# Sheet1.net
KiCad netlist of a schematic drawn in Altium Designer
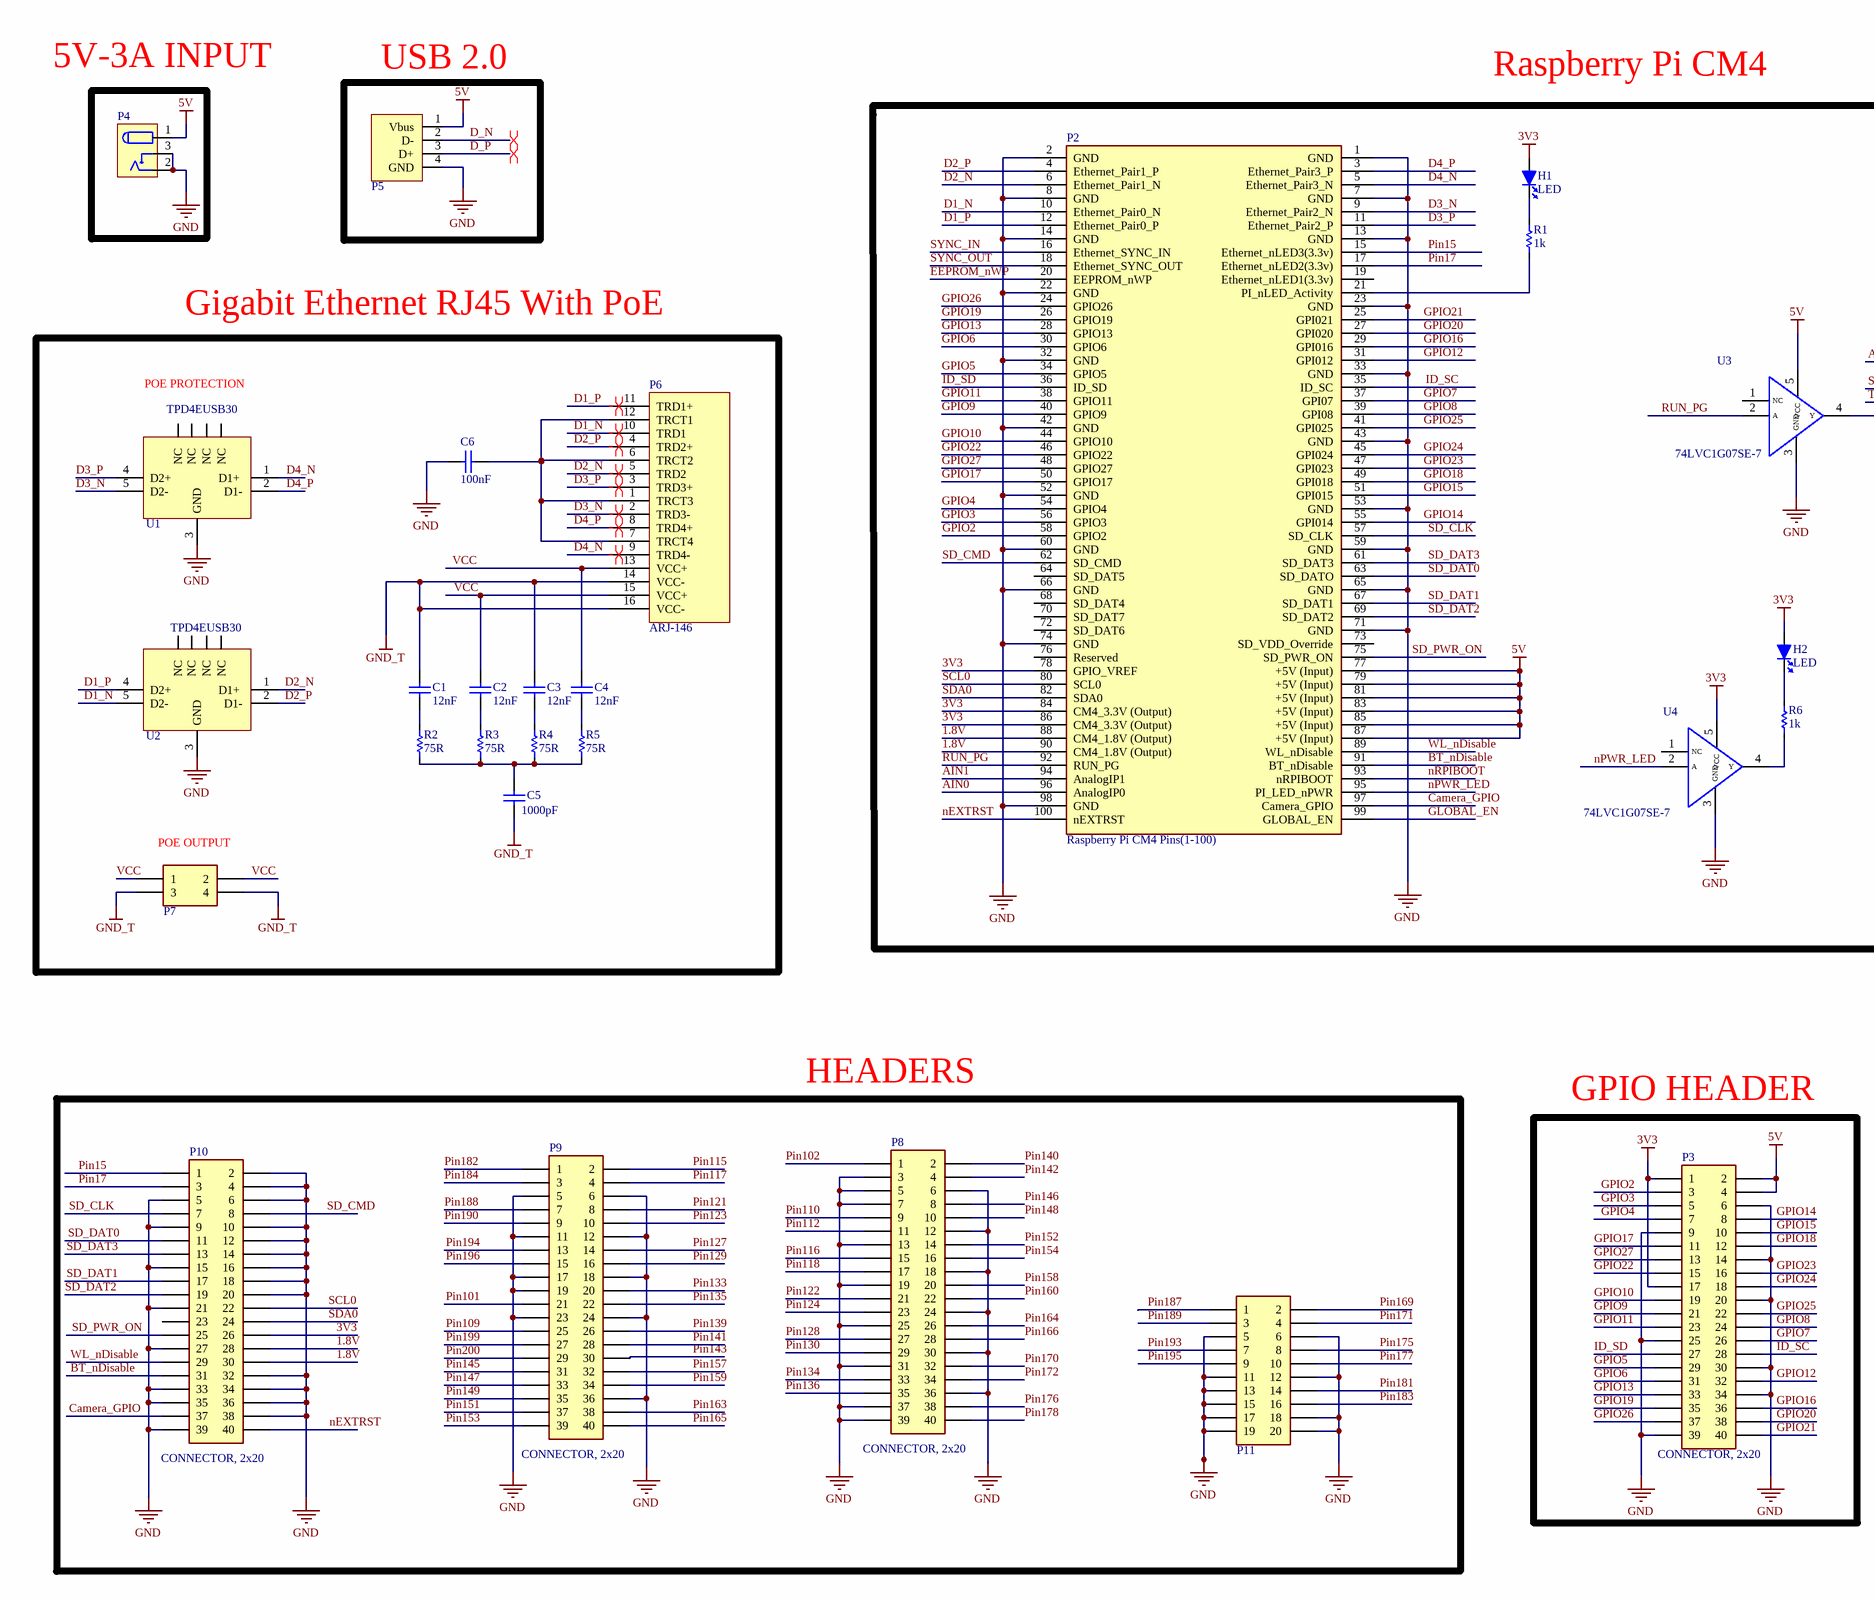
[diagram p0: Sheet1.SchDoc, left]
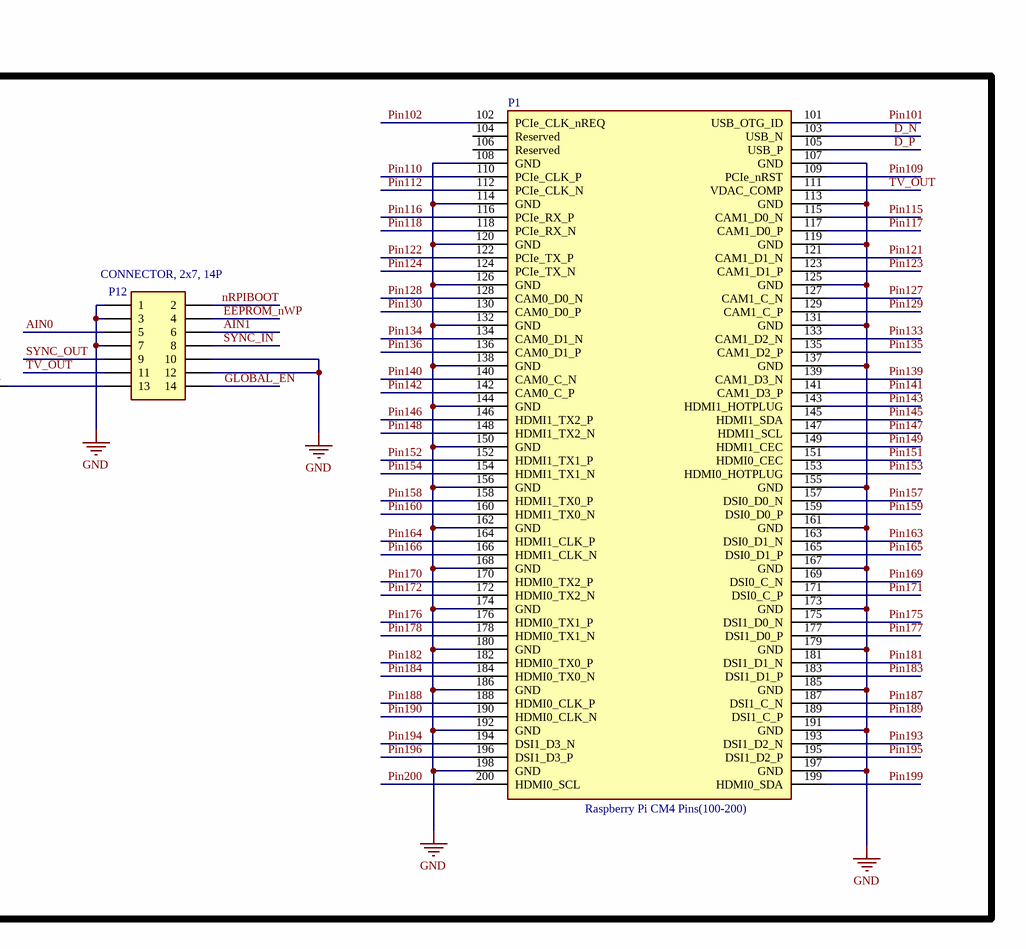
[diagram p1: Sheet1.SchDoc, right]

(export (version "E")
  (design (tool "Eeschema 10.0.6"))
  (components
    (comp (ref "C1")
      (value "12nF")
      (footprint "CC1608-0603L")
      (description "CAP CER 12nF 100V X7R 0603")
      (fields
        (field (name "MANUFACTURER") "KYOCERA AVX")
        (field (name "MANUFACTURER PART NUMBER") "06031C123KAT2A")
      )
      (libsource (lib "SchLibrary") (part "CAPACITOR NON-POL"))
    )
    (comp (ref "C2")
      (value "12nF")
      (footprint "CC1608-0603L")
      (description "CAP CER 12nF 100V X7R 0603")
      (fields
        (field (name "MANUFACTURER") "KYOCERA AVX")
        (field (name "MANUFACTURER PART NUMBER") "06031C123KAT2A")
      )
      (libsource (lib "SchLibrary") (part "CAPACITOR NON-POL"))
    )
    (comp (ref "C3")
      (value "12nF")
      (footprint "CC1608-0603L")
      (description "CAP CER 12nF 100V X7R 0603")
      (fields
        (field (name "MANUFACTURER") "KYOCERA AVX")
        (field (name "MANUFACTURER PART NUMBER") "06031C123KAT2A")
      )
      (libsource (lib "SchLibrary") (part "CAPACITOR NON-POL"))
    )
    (comp (ref "C4")
      (value "12nF")
      (footprint "CC1608-0603L")
      (description "CAP CER 12nF 100V X7R 0603")
      (fields
        (field (name "MANUFACTURER") "KYOCERA AVX")
        (field (name "MANUFACTURER PART NUMBER") "06031C123KAT2A")
      )
      (libsource (lib "SchLibrary") (part "CAPACITOR NON-POL"))
    )
    (comp (ref "C5")
      (value "1000pF")
      (footprint "CC3225-1210L")
      (description "CAP CER 1000pF 2KV X7R 1210")
      (fields
        (field (name "MANUFACTURER") "Johanson Dielectrics Inc.")
        (field (name "MANUFACTURER PART NUMBER") "VPDF202W102K1GV001E")
      )
      (libsource (lib "SchLibrary") (part "CAPACITOR NON-POL"))
    )
    (comp (ref "C6")
      (value "100nF")
      (footprint "CC1608-0603L")
      (description "MLCC (1608) 0603 100nF 50VDC ±10% X7R")
      (fields
        (field (name "MANUFACTURER") "YAGEO")
        (field (name "MANUFACTURER PART NUMBER") "CC0603KRX7R9BB104")
      )
      (libsource (lib "SchLibrary") (part "CAPACITOR NON-POL"))
    )
    (comp (ref "H1")
      (value "LED")
      (footprint "LED0805")
      (description "LED SMD 0805 GREEN 18-45mcd 140° WATER CLEAR")
      (fields
        (field (name "MANUFACTURER") "EVERLIGHT")
        (field (name "MANUFACTURER PART NUMBER") "17-21/G6C-FM1N2B/4T")
      )
      (libsource (lib "SchLibrary") (part "LED"))
    )
    (comp (ref "H2")
      (value "LED")
      (footprint "LED0805")
      (description "LED SMD 0805 RED 45~112mcd 120C")
      (fields
        (field (name "MANUFACTURER") "EVERLIGHT")
        (field (name "MANUFACTURER PART NUMBER") "17-21/R6C-AP1Q2L/4T")
      )
      (libsource (lib "SchLibrary") (part "LED"))
    )
    (comp (ref "P1")
      (value "Raspberry Pi CM4 Pins(100-200)")
      (footprint "(2)HRS_DF40HC(3.0)-100DS-0.4P(2)")
      (description "Connector , 2*50")
      (fields
        (field (name "MANUFACTURER") "Hirose Electric")
        (field (name "MANUFACTURER PART NUMBER") "DF40HC(3.0)-100DS-0.4V(51)")
      )
      (libsource (lib "SchLibrary") (part "Raspberry Pi CM4 Pins(100-200)"))
    )
    (comp (ref "P2")
      (value "Raspberry Pi CM4 Pins(1-100)")
      (footprint "HRS_DF40HC(3.0)-100DS-0.4P - duplicate")
      (description "Connector , 2*50")
      (fields
        (field (name "MANUFACTURER") "Hirose Electric")
        (field (name "MANUFACTURER PART NUMBER") "DF40HC(3.0)-100DS-0.4V(51)")
      )
      (libsource (lib "SchLibrary") (part "Raspberry Pi CM4 Pins(1-100)"))
    )
    (comp (ref "P3")
      (value "CONNECTOR, 2x20")
      (footprint "HDR_FEMALE_2.54MM_2x20_40P")
      (description "CONNECTOR, 2x20, 40P")
      (fields
        (field (name "MANUFACTURER") "Würth Elektronik")
        (field (name "MANUFACTURER PART NUMBER") "61304021821")
      )
      (libsource (lib "SchLibrary") (part "CONNECTOR, 2x20"))
    )
    (comp (ref "P4")
      (value "CONNECTOR_BARREL_JACK")
      (footprint "PowerJack_GCT_DCJ200-10-A-XX-K_REVA")
      (description "Power Barrel Connector Jack 2.05mm ID (0.081\"), 5.50mm OD (0.217\") Through Hole, Right Angle")
      (fields
        (field (name "MANUFACTURER") "GCT")
        (field (name "MANUFACTURER PART NUMBER") "DCJ200-10-A-K1-K")
      )
      (libsource (lib "SchLibrary") (part "CONNECTOR_BARREL_JACK"))
    )
    (comp (ref "P5")
      (value "61400416021")
      (footprint "61400416021")
      (description "USB-A (USB TYPE-A) USB 2.0 Receptacle Connector 4 Position Through Hole, Right Angle")
      (fields (field (name "MANUFACTURER") "Würth Elektronik"))
      (libsource (lib "USB20TYPE_A") (part "61400416021"))
    )
    (comp (ref "P6")
      (value "ARJ-146")
      (footprint "ARJ-146")
      (description "1 Port RJ45 Through Hole 10/100/1000 Base-T, AutoMDIX, Power over Ethernet (PoE)")
      (fields (field (name "MANUFACTURER") "Abracon LLC"))
      (libsource (lib "Connector_Ethernet_RJ45") (part "ARJ-146"))
    )
    (comp (ref "P7")
      (value "CONNECTOR, 2x2, 4P")
      (footprint "HDR_MALE_2X2_4P_2.54MM_180")
      (description "Male Header, 2x2, 4P , 2,54mm")
      (fields
        (field (name "MANUFACTURER") "KLS ELECTRONIC")
        (field (name "MANUFACTURER PART NUMBER") "L-KLS1-207-2-04-S")
      )
      (libsource (lib "SchLibrary") (part "CONNECTOR, 2x2, 4P"))
    )
    (comp (ref "P8")
      (value "CONNECTOR, 2x20")
      (footprint "HDR_FEMALE_2.54MM_2x20_40P")
      (description "CONNECTOR, 2x20, 40P")
      (fields
        (field (name "MANUFACTURER") "Würth Elektronik")
        (field (name "MANUFACTURER PART NUMBER") "61304021821")
      )
      (libsource (lib "SchLibrary") (part "CONNECTOR, 2x20"))
    )
    (comp (ref "P9")
      (value "CONNECTOR, 2x20")
      (footprint "HDR_FEMALE_2.54MM_2x20_40P")
      (description "CONNECTOR, 2x20, 40P")
      (fields
        (field (name "MANUFACTURER") "Würth Elektronik")
        (field (name "MANUFACTURER PART NUMBER") "61304021821")
      )
      (libsource (lib "SchLibrary") (part "CONNECTOR, 2x20"))
    )
    (comp (ref "P10")
      (value "CONNECTOR, 2x20")
      (footprint "HDR_FEMALE_2.54MM_2x20_40P")
      (description "CONNECTOR, 2x20, 40P")
      (fields
        (field (name "MANUFACTURER") "Würth Elektronik")
        (field (name "MANUFACTURER PART NUMBER") "61304021821")
      )
      (libsource (lib "SchLibrary") (part "CONNECTOR, 2x20"))
    )
    (comp (ref "P11")
      (value "CONNECTOR, 2x10, 20P")
      (footprint "HDR_MALE_2X10_20P_2.54MM_180")
      (fields
        (field (name "MANUFACTURER") "CONNFLY")
        (field (name "MANUFACTURER PART NUMBER") "DS1021-2X10SF11-B")
      )
      (libsource (lib "SchLibrary") (part "CONNECTOR, 2x10, 20P"))
    )
    (comp (ref "P12")
      (value "CONNECTOR, 2x7, 14P")
      (footprint "HDR_MALE_2X7_14P_2.54MM_180")
      (fields
        (field (name "MANUFACTURER") "CONNFLY")
        (field (name "MANUFACTURER PART NUMBER") "DS1004-2X7F14")
      )
      (libsource (lib "SchLibrary") (part "CONNECTOR, 2x7, 14P"))
    )
    (comp (ref "R1")
      (value "1k")
      (footprint "CR1608-0603L")
      (description "RES.(1608) 0603 1K Ohms 5% 1/10W 100PPM SMT")
      (fields
        (field (name "MANUFACTURER") "YAGEO")
        (field (name "MANUFACTURER PART NUMBER") "RC0603JR-071KL")
      )
      (libsource (lib "SchLibrary") (part "RESISTOR"))
    )
    (comp (ref "R2")
      (value "75R")
      (footprint "CR3216-1206l")
      (description "RES.(3216) 1206 75 Ohms 5% 1/4W-S 200PPM")
      (fields
        (field (name "MANUFACTURER") "ROYALOHM")
        (field (name "MANUFACTURER PART NUMBER") "1206S4J0750T5E")
      )
      (libsource (lib "SchLibrary") (part "RESISTOR"))
    )
    (comp (ref "R3")
      (value "75R")
      (footprint "CR3216-1206l")
      (description "RES.(3216) 1206 75 Ohms 5% 1/4W-S 200PPM")
      (fields
        (field (name "MANUFACTURER") "ROYALOHM")
        (field (name "MANUFACTURER PART NUMBER") "1206S4J0750T5E")
      )
      (libsource (lib "SchLibrary") (part "RESISTOR"))
    )
    (comp (ref "R4")
      (value "75R")
      (footprint "CR3216-1206l")
      (description "RES.(3216) 1206 75 Ohms 5% 1/4W-S 200PPM")
      (fields
        (field (name "MANUFACTURER") "ROYALOHM")
        (field (name "MANUFACTURER PART NUMBER") "1206S4J0750T5E")
      )
      (libsource (lib "SchLibrary") (part "RESISTOR"))
    )
    (comp (ref "R5")
      (value "75R")
      (footprint "CR3216-1206l")
      (description "RES.(3216) 1206 75 Ohms 5% 1/4W-S 200PPM")
      (fields
        (field (name "MANUFACTURER") "ROYALOHM")
        (field (name "MANUFACTURER PART NUMBER") "1206S4J0750T5E")
      )
      (libsource (lib "SchLibrary") (part "RESISTOR"))
    )
    (comp (ref "R6")
      (value "1k")
      (footprint "CR1608-0603L")
      (description "RES.(1608) 0603 1K Ohms 5% 1/10W 100PPM SMT")
      (fields
        (field (name "MANUFACTURER") "YAGEO")
        (field (name "MANUFACTURER PART NUMBER") "RC0603JR-071KL")
      )
      (libsource (lib "SchLibrary") (part "RESISTOR"))
    )
    (comp (ref "U1")
      (value "TPD4EUSB30")
      (footprint "USON50P250X55-10N")
      (description "TVS DIODE 5.5VWM 8VC 10USON")
      (fields
        (field (name "MANUFACTURER") "Texas Instruments")
        (field (name "MANUFACTURER PART NUMBER") "TPD4EUSB30DQAR")
      )
      (libsource (lib "IC_Diode") (part "TPD4EUSB30"))
    )
    (comp (ref "U2")
      (value "TPD4EUSB30")
      (footprint "USON50P250X55-10N")
      (description "TVS DIODE 5.5VWM 8VC 10USON")
      (fields
        (field (name "MANUFACTURER") "Texas Instruments")
        (field (name "MANUFACTURER PART NUMBER") "TPD4EUSB30DQAR")
      )
      (libsource (lib "IC_Diode") (part "TPD4EUSB30"))
    )
    (comp (ref "U3")
      (value "74LVC1G07SE-7")
      (footprint "SOT35365P215X100-5N")
      (description "IC BUF NON-INVERT 5.5V")
      (fields (field (name "MANUFACTURER") "DIODES"))
      (libsource (lib "IC_Buffer") (part "74LVC1G07SE-7"))
    )
    (comp (ref "U4")
      (value "74LVC1G07SE-7")
      (footprint "SOT35365P215X100-5N")
      (description "IC BUF NON-INVERT 5.5V")
      (fields (field (name "MANUFACTURER") "DIODES"))
      (libsource (lib "IC_Buffer") (part "74LVC1G07SE-7"))
    )
  )
  (nets
    (net (code "1") (name "/1.8V") (class "Default")
      (node (ref "P10") (pin "28") (pinfunction "28_28") (pintype "passive"))
      (node (ref "P10") (pin "30") (pinfunction "30_30") (pintype "passive"))
      (node (ref "P2") (pin "88") (pinfunction "CM4_1.8V_(Output)_88") (pintype "passive"))
      (node (ref "P2") (pin "90") (pinfunction "CM4_1.8V_(Output)_90") (pintype "passive"))
    )
    (net (code "2") (name "/AIN0") (class "Default")
      (node (ref "P12") (pin "5") (pinfunction "5_5") (pintype "passive"))
      (node (ref "P2") (pin "96") (pinfunction "AnalogIP0_96") (pintype "passive"))
    )
    (net (code "3") (name "/AIN1") (class "Default")
      (node (ref "P12") (pin "6") (pinfunction "6_6") (pintype "passive"))
      (node (ref "P2") (pin "94") (pinfunction "AnalogIP1_94") (pintype "passive"))
    )
    (net (code "4") (name "/BT_nDisable") (class "Default")
      (node (ref "P10") (pin "31") (pinfunction "31_31") (pintype "passive"))
      (node (ref "P2") (pin "91") (pinfunction "BT_nDisable_91") (pintype "passive"))
    )
    (net (code "5") (name "/Camera_GPIO") (class "Default")
      (node (ref "P10") (pin "37") (pinfunction "37_37") (pintype "passive"))
      (node (ref "P2") (pin "97") (pinfunction "Camera_GPIO_97") (pintype "passive"))
    )
    (net (code "6") (name "/D1_N") (class "Default")
      (node (ref "P2") (pin "10") (pinfunction "Ethernet_Pair0_N_10") (pintype "passive"))
      (node (ref "P6") (pin "10") (pinfunction "TRD1_10") (pintype "passive"))
      (node (ref "U2") (pin "5") (pinfunction "D2-_5") (pintype "passive"))
    )
    (net (code "7") (name "/D1_P") (class "Default")
      (node (ref "P2") (pin "12") (pinfunction "Ethernet_Pair0_P_12") (pintype "passive"))
      (node (ref "P6") (pin "11") (pinfunction "TRD1+_11") (pintype "passive"))
      (node (ref "U2") (pin "4") (pinfunction "D2+_4") (pintype "passive"))
    )
    (net (code "8") (name "/D2_N") (class "Default")
      (node (ref "P2") (pin "6") (pinfunction "Ethernet_Pair1_N_6") (pintype "passive"))
      (node (ref "P6") (pin "5") (pinfunction "TRD2_5") (pintype "passive"))
      (node (ref "U2") (pin "1") (pinfunction "D1+_1") (pintype "passive"))
    )
    (net (code "9") (name "/D2_P") (class "Default")
      (node (ref "P2") (pin "4") (pinfunction "Ethernet_Pair1_P_4") (pintype "passive"))
      (node (ref "P6") (pin "4") (pinfunction "TRD2+_4") (pintype "passive"))
      (node (ref "U2") (pin "2") (pinfunction "D1-_2") (pintype "passive"))
    )
    (net (code "10") (name "/D3_N") (class "Default")
      (node (ref "P2") (pin "9") (pinfunction "Ethernet_Pair2_N_9") (pintype "passive"))
      (node (ref "P6") (pin "2") (pinfunction "TRD3-_2") (pintype "passive"))
      (node (ref "U1") (pin "5") (pinfunction "D2-_5") (pintype "passive"))
    )
    (net (code "11") (name "/D3_P") (class "Default")
      (node (ref "P2") (pin "11") (pinfunction "Ethernet_Pair2_P_11") (pintype "passive"))
      (node (ref "P6") (pin "3") (pinfunction "TRD3+_3") (pintype "passive"))
      (node (ref "U1") (pin "4") (pinfunction "D2+_4") (pintype "passive"))
    )
    (net (code "12") (name "/D4_N") (class "Default")
      (node (ref "P2") (pin "5") (pinfunction "Ethernet_Pair3_N_5") (pintype "passive"))
      (node (ref "P6") (pin "9") (pinfunction "TRD4-_9") (pintype "passive"))
      (node (ref "U1") (pin "1") (pinfunction "D1+_1") (pintype "passive"))
    )
    (net (code "13") (name "/D4_P") (class "Default")
      (node (ref "P2") (pin "3") (pinfunction "Ethernet_Pair3_P_3") (pintype "passive"))
      (node (ref "P6") (pin "8") (pinfunction "TRD4+_8") (pintype "passive"))
      (node (ref "U1") (pin "2") (pinfunction "D1-_2") (pintype "passive"))
    )
    (net (code "14") (name "/D_N") (class "Default")
      (node (ref "P1") (pin "103") (pinfunction "USB_N_103") (pintype "passive"))
      (node (ref "P5") (pin "2") (pinfunction "D-_2") (pintype "passive"))
    )
    (net (code "15") (name "/D_P") (class "Default")
      (node (ref "P1") (pin "105") (pinfunction "USB_P_105") (pintype "passive"))
      (node (ref "P5") (pin "3") (pinfunction "D+_3") (pintype "passive"))
    )
    (net (code "16") (name "/EEPROM_nWP") (class "Default")
      (node (ref "P12") (pin "4") (pinfunction "4_4") (pintype "passive"))
      (node (ref "P2") (pin "20") (pinfunction "EEPROM_nWP_20") (pintype "passive"))
    )
    (net (code "17") (name "/GLOBAL_EN") (class "Default")
      (node (ref "P12") (pin "14") (pinfunction "14_14") (pintype "passive"))
      (node (ref "P2") (pin "99") (pinfunction "GLOBAL_EN_99") (pintype "passive"))
    )
    (net (code "18") (name "/GPIO2") (class "Default")
      (node (ref "P2") (pin "58") (pinfunction "GPIO2_58") (pintype "passive"))
      (node (ref "P3") (pin "3") (pinfunction "3_3") (pintype "passive"))
    )
    (net (code "19") (name "/GPIO3") (class "Default")
      (node (ref "P2") (pin "56") (pinfunction "GPIO3_56") (pintype "passive"))
      (node (ref "P3") (pin "5") (pinfunction "5_5") (pintype "passive"))
    )
    (net (code "20") (name "/GPIO4") (class "Default")
      (node (ref "P2") (pin "54") (pinfunction "GPIO4_54") (pintype "passive"))
      (node (ref "P3") (pin "7") (pinfunction "7_7") (pintype "passive"))
    )
    (net (code "21") (name "/GPIO5") (class "Default")
      (node (ref "P2") (pin "34") (pinfunction "GPIO5_34") (pintype "passive"))
      (node (ref "P3") (pin "29") (pinfunction "29_29") (pintype "passive"))
    )
    (net (code "22") (name "/GPIO6") (class "Default")
      (node (ref "P2") (pin "30") (pinfunction "GPIO6_30") (pintype "passive"))
      (node (ref "P3") (pin "31") (pinfunction "31_31") (pintype "passive"))
    )
    (net (code "23") (name "/GPIO7") (class "Default")
      (node (ref "P2") (pin "37") (pinfunction "GPI07_37") (pintype "passive"))
      (node (ref "P3") (pin "26") (pinfunction "26_26") (pintype "passive"))
    )
    (net (code "24") (name "/GPIO8") (class "Default")
      (node (ref "P2") (pin "39") (pinfunction "GPI08_39") (pintype "passive"))
      (node (ref "P3") (pin "24") (pinfunction "24_24") (pintype "passive"))
    )
    (net (code "25") (name "/GPIO9") (class "Default")
      (node (ref "P2") (pin "40") (pinfunction "GPIO9_40") (pintype "passive"))
      (node (ref "P3") (pin "21") (pinfunction "21_21") (pintype "passive"))
    )
    (net (code "26") (name "/GPIO10") (class "Default")
      (node (ref "P2") (pin "44") (pinfunction "GPIO10_44") (pintype "passive"))
      (node (ref "P3") (pin "19") (pinfunction "19_19") (pintype "passive"))
    )
    (net (code "27") (name "/GPIO11") (class "Default")
      (node (ref "P2") (pin "38") (pinfunction "GPIO11_38") (pintype "passive"))
      (node (ref "P3") (pin "23") (pinfunction "23_23") (pintype "passive"))
    )
    (net (code "28") (name "/GPIO12") (class "Default")
      (node (ref "P2") (pin "31") (pinfunction "GPI012_31") (pintype "passive"))
      (node (ref "P3") (pin "32") (pinfunction "32_32") (pintype "passive"))
    )
    (net (code "29") (name "/GPIO13") (class "Default")
      (node (ref "P2") (pin "28") (pinfunction "GPIO13_28") (pintype "passive"))
      (node (ref "P3") (pin "33") (pinfunction "33_33") (pintype "passive"))
    )
    (net (code "30") (name "/GPIO14") (class "Default")
      (node (ref "P2") (pin "55") (pinfunction "GPI014_55") (pintype "passive"))
      (node (ref "P3") (pin "8") (pinfunction "8_8") (pintype "passive"))
    )
    (net (code "31") (name "/GPIO15") (class "Default")
      (node (ref "P2") (pin "51") (pinfunction "GPI015_51") (pintype "passive"))
      (node (ref "P3") (pin "10") (pinfunction "10_10") (pintype "passive"))
    )
    (net (code "32") (name "/GPIO16") (class "Default")
      (node (ref "P2") (pin "29") (pinfunction "GPI016_29") (pintype "passive"))
      (node (ref "P3") (pin "36") (pinfunction "36_36") (pintype "passive"))
    )
    (net (code "33") (name "/GPIO17") (class "Default")
      (node (ref "P2") (pin "50") (pinfunction "GPIO17_50") (pintype "passive"))
      (node (ref "P3") (pin "11") (pinfunction "11_11") (pintype "passive"))
    )
    (net (code "34") (name "/GPIO18") (class "Default")
      (node (ref "P2") (pin "49") (pinfunction "GPI018_49") (pintype "passive"))
      (node (ref "P3") (pin "12") (pinfunction "12_12") (pintype "passive"))
    )
    (net (code "35") (name "/GPIO19") (class "Default")
      (node (ref "P2") (pin "26") (pinfunction "GPIO19_26") (pintype "passive"))
      (node (ref "P3") (pin "35") (pinfunction "35_35") (pintype "passive"))
    )
    (net (code "36") (name "/GPIO20") (class "Default")
      (node (ref "P2") (pin "27") (pinfunction "GPI020_27") (pintype "passive"))
      (node (ref "P3") (pin "38") (pinfunction "38_38") (pintype "passive"))
    )
    (net (code "37") (name "/GPIO21") (class "Default")
      (node (ref "P2") (pin "25") (pinfunction "GPI021_25") (pintype "passive"))
      (node (ref "P3") (pin "40") (pinfunction "40_40") (pintype "passive"))
    )
    (net (code "38") (name "/GPIO22") (class "Default")
      (node (ref "P2") (pin "46") (pinfunction "GPIO22_46") (pintype "passive"))
      (node (ref "P3") (pin "15") (pinfunction "15_15") (pintype "passive"))
    )
    (net (code "39") (name "/GPIO23") (class "Default")
      (node (ref "P2") (pin "47") (pinfunction "GPI023_47") (pintype "passive"))
      (node (ref "P3") (pin "16") (pinfunction "16_16") (pintype "passive"))
    )
    (net (code "40") (name "/GPIO24") (class "Default")
      (node (ref "P2") (pin "45") (pinfunction "GPI024_45") (pintype "passive"))
      (node (ref "P3") (pin "18") (pinfunction "18_18") (pintype "passive"))
    )
    (net (code "41") (name "/GPIO25") (class "Default")
      (node (ref "P2") (pin "41") (pinfunction "GPI025_41") (pintype "passive"))
      (node (ref "P3") (pin "22") (pinfunction "22_22") (pintype "passive"))
    )
    (net (code "42") (name "/GPIO26") (class "Default")
      (node (ref "P2") (pin "24") (pinfunction "GPIO26_24") (pintype "passive"))
      (node (ref "P3") (pin "37") (pinfunction "37_37") (pintype "passive"))
    )
    (net (code "43") (name "/GPIO27") (class "Default")
      (node (ref "P2") (pin "48") (pinfunction "GPIO27_48") (pintype "passive"))
      (node (ref "P3") (pin "13") (pinfunction "13_13") (pintype "passive"))
    )
    (net (code "44") (name "/ID_SC") (class "Default")
      (node (ref "P2") (pin "35") (pinfunction "ID_SC_35") (pintype "passive"))
      (node (ref "P3") (pin "28") (pinfunction "28_28") (pintype "passive"))
    )
    (net (code "45") (name "/ID_SD") (class "Default")
      (node (ref "P2") (pin "36") (pinfunction "ID_SD_36") (pintype "passive"))
      (node (ref "P3") (pin "27") (pinfunction "27_27") (pintype "passive"))
    )
    (net (code "46") (name "/Pin15") (class "Default")
      (node (ref "P10") (pin "1") (pinfunction "1_1") (pintype "passive"))
      (node (ref "P2") (pin "15") (pinfunction "Ethernet_nLED3(3.3v)_15") (pintype "passive"))
    )
    (net (code "47") (name "/Pin17") (class "Default")
      (node (ref "P10") (pin "3") (pinfunction "3_3") (pintype "passive"))
      (node (ref "P2") (pin "17") (pinfunction "Ethernet_nLED2(3.3v)_17") (pintype "passive"))
    )
    (net (code "48") (name "/Pin101") (class "Default")
      (node (ref "P1") (pin "101") (pinfunction "USB_OTG_ID_101") (pintype "passive"))
      (node (ref "P9") (pin "21") (pinfunction "21_21") (pintype "passive"))
    )
    (net (code "49") (name "/Pin102") (class "Default")
      (node (ref "P1") (pin "102") (pinfunction "PCIe_CLK_nREQ_102") (pintype "passive"))
      (node (ref "P8") (pin "1") (pinfunction "1_1") (pintype "passive"))
    )
    (net (code "50") (name "/Pin109") (class "Default")
      (node (ref "P1") (pin "109") (pinfunction "PCIe_nRST_109") (pintype "passive"))
      (node (ref "P9") (pin "25") (pinfunction "25_25") (pintype "passive"))
    )
    (net (code "51") (name "/Pin110") (class "Default")
      (node (ref "P1") (pin "110") (pinfunction "PCIe_CLK_P_110") (pintype "passive"))
      (node (ref "P8") (pin "9") (pinfunction "9_9") (pintype "passive"))
    )
    (net (code "52") (name "/Pin112") (class "Default")
      (node (ref "P1") (pin "112") (pinfunction "PCIe_CLK_N_112") (pintype "passive"))
      (node (ref "P8") (pin "11") (pinfunction "11_11") (pintype "passive"))
    )
    (net (code "53") (name "/Pin115") (class "Default")
      (node (ref "P1") (pin "115") (pinfunction "CAM1_D0_N_115") (pintype "passive"))
      (node (ref "P9") (pin "2") (pinfunction "2_2") (pintype "passive"))
    )
    (net (code "54") (name "/Pin116") (class "Default")
      (node (ref "P1") (pin "116") (pinfunction "PCIe_RX_P_116") (pintype "passive"))
      (node (ref "P8") (pin "15") (pinfunction "15_15") (pintype "passive"))
    )
    (net (code "55") (name "/Pin117") (class "Default")
      (node (ref "P1") (pin "117") (pinfunction "CAM1_D0_P_117") (pintype "passive"))
      (node (ref "P9") (pin "4") (pinfunction "4_4") (pintype "passive"))
    )
    (net (code "56") (name "/Pin118") (class "Default")
      (node (ref "P1") (pin "118") (pinfunction "PCIe_RX_N_118") (pintype "passive"))
      (node (ref "P8") (pin "17") (pinfunction "17_17") (pintype "passive"))
    )
    (net (code "57") (name "/Pin121") (class "Default")
      (node (ref "P1") (pin "121") (pinfunction "CAM1_D1_N_121") (pintype "passive"))
      (node (ref "P9") (pin "8") (pinfunction "8_8") (pintype "passive"))
    )
    (net (code "58") (name "/Pin122") (class "Default")
      (node (ref "P1") (pin "122") (pinfunction "PCIe_TX_P_122") (pintype "passive"))
      (node (ref "P8") (pin "21") (pinfunction "21_21") (pintype "passive"))
    )
    (net (code "59") (name "/Pin123") (class "Default")
      (node (ref "P1") (pin "123") (pinfunction "CAM1_D1_P_123") (pintype "passive"))
      (node (ref "P9") (pin "10") (pinfunction "10_10") (pintype "passive"))
    )
    (net (code "60") (name "/Pin124") (class "Default")
      (node (ref "P1") (pin "124") (pinfunction "PCIe_TX_N_124") (pintype "passive"))
      (node (ref "P8") (pin "23") (pinfunction "23_23") (pintype "passive"))
    )
    (net (code "61") (name "/Pin127") (class "Default")
      (node (ref "P1") (pin "127") (pinfunction "CAM1_C_N_127") (pintype "passive"))
      (node (ref "P9") (pin "14") (pinfunction "14_14") (pintype "passive"))
    )
    (net (code "62") (name "/Pin128") (class "Default")
      (node (ref "P1") (pin "128") (pinfunction "CAM0_D0_N_128") (pintype "passive"))
      (node (ref "P8") (pin "27") (pinfunction "27_27") (pintype "passive"))
    )
    (net (code "63") (name "/Pin129") (class "Default")
      (node (ref "P1") (pin "129") (pinfunction "CAM1_C_P_129") (pintype "passive"))
      (node (ref "P9") (pin "16") (pinfunction "16_16") (pintype "passive"))
    )
    (net (code "64") (name "/Pin130") (class "Default")
      (node (ref "P1") (pin "130") (pinfunction "CAM0_D0_P_130") (pintype "passive"))
      (node (ref "P8") (pin "29") (pinfunction "29_29") (pintype "passive"))
    )
    (net (code "65") (name "/Pin133") (class "Default")
      (node (ref "P1") (pin "133") (pinfunction "CAM1_D2_N_133") (pintype "passive"))
      (node (ref "P9") (pin "20") (pinfunction "20_20") (pintype "passive"))
    )
    (net (code "66") (name "/Pin134") (class "Default")
      (node (ref "P1") (pin "134") (pinfunction "CAM0_D1_N_134") (pintype "passive"))
      (node (ref "P8") (pin "33") (pinfunction "33_33") (pintype "passive"))
    )
    (net (code "67") (name "/Pin135") (class "Default")
      (node (ref "P1") (pin "135") (pinfunction "CAM1_D2_P_135") (pintype "passive"))
      (node (ref "P9") (pin "22") (pinfunction "22_22") (pintype "passive"))
    )
    (net (code "68") (name "/Pin136") (class "Default")
      (node (ref "P1") (pin "136") (pinfunction "CAM0_D1_P_136") (pintype "passive"))
      (node (ref "P8") (pin "35") (pinfunction "35_35") (pintype "passive"))
    )
    (net (code "69") (name "/Pin139") (class "Default")
      (node (ref "P1") (pin "139") (pinfunction "CAM1_D3_N_139") (pintype "passive"))
      (node (ref "P9") (pin "26") (pinfunction "26_26") (pintype "passive"))
    )
    (net (code "70") (name "/Pin140") (class "Default")
      (node (ref "P1") (pin "140") (pinfunction "CAM0_C_N_140") (pintype "passive"))
      (node (ref "P8") (pin "2") (pinfunction "2_2") (pintype "passive"))
    )
    (net (code "71") (name "/Pin141") (class "Default")
      (node (ref "P1") (pin "141") (pinfunction "CAM1_D3_P_141") (pintype "passive"))
      (node (ref "P9") (pin "28") (pinfunction "28_28") (pintype "passive"))
    )
    (net (code "72") (name "/Pin142") (class "Default")
      (node (ref "P1") (pin "142") (pinfunction "CAM0_C_P_142") (pintype "passive"))
      (node (ref "P8") (pin "4") (pinfunction "4_4") (pintype "passive"))
    )
    (net (code "73") (name "/Pin143") (class "Default")
      (node (ref "P1") (pin "143") (pinfunction "HDMI1_HOTPLUG_143") (pintype "passive"))
      (node (ref "P9") (pin "30") (pinfunction "30_30") (pintype "passive"))
    )
    (net (code "74") (name "/Pin145") (class "Default")
      (node (ref "P1") (pin "145") (pinfunction "HDMI1_SDA_145") (pintype "passive"))
      (node (ref "P9") (pin "31") (pinfunction "31_31") (pintype "passive"))
    )
    (net (code "75") (name "/Pin146") (class "Default")
      (node (ref "P1") (pin "146") (pinfunction "HDMI1_TX2_P_146") (pintype "passive"))
      (node (ref "P8") (pin "8") (pinfunction "8_8") (pintype "passive"))
    )
    (net (code "76") (name "/Pin147") (class "Default")
      (node (ref "P1") (pin "147") (pinfunction "HDMI1_SCL_147") (pintype "passive"))
      (node (ref "P9") (pin "33") (pinfunction "33_33") (pintype "passive"))
    )
    (net (code "77") (name "/Pin148") (class "Default")
      (node (ref "P1") (pin "148") (pinfunction "HDMI1_TX2_N_148") (pintype "passive"))
      (node (ref "P8") (pin "10") (pinfunction "10_10") (pintype "passive"))
    )
    (net (code "78") (name "/Pin149") (class "Default")
      (node (ref "P1") (pin "149") (pinfunction "HDMI1_CEC_149") (pintype "passive"))
      (node (ref "P9") (pin "35") (pinfunction "35_35") (pintype "passive"))
    )
    (net (code "79") (name "/Pin151") (class "Default")
      (node (ref "P1") (pin "151") (pinfunction "HDMI0_CEC_151") (pintype "passive"))
      (node (ref "P9") (pin "37") (pinfunction "37_37") (pintype "passive"))
    )
    (net (code "80") (name "/Pin152") (class "Default")
      (node (ref "P1") (pin "152") (pinfunction "HDMI1_TX1_P_152") (pintype "passive"))
      (node (ref "P8") (pin "14") (pinfunction "14_14") (pintype "passive"))
    )
    (net (code "81") (name "/Pin153") (class "Default")
      (node (ref "P1") (pin "153") (pinfunction "HDMI0_HOTPLUG_153") (pintype "passive"))
      (node (ref "P9") (pin "39") (pinfunction "39_39") (pintype "passive"))
    )
    (net (code "82") (name "/Pin154") (class "Default")
      (node (ref "P1") (pin "154") (pinfunction "HDMI1_TX1_N_154") (pintype "passive"))
      (node (ref "P8") (pin "16") (pinfunction "16_16") (pintype "passive"))
    )
    (net (code "83") (name "/Pin157") (class "Default")
      (node (ref "P1") (pin "157") (pinfunction "DSI0_D0_N_157") (pintype "passive"))
      (node (ref "P9") (pin "32") (pinfunction "32_32") (pintype "passive"))
    )
    (net (code "84") (name "/Pin158") (class "Default")
      (node (ref "P1") (pin "158") (pinfunction "HDMI1_TX0_P_158") (pintype "passive"))
      (node (ref "P8") (pin "20") (pinfunction "20_20") (pintype "passive"))
    )
    (net (code "85") (name "/Pin159") (class "Default")
      (node (ref "P1") (pin "159") (pinfunction "DSI0_D0_P_159") (pintype "passive"))
      (node (ref "P9") (pin "34") (pinfunction "34_34") (pintype "passive"))
    )
    (net (code "86") (name "/Pin160") (class "Default")
      (node (ref "P1") (pin "160") (pinfunction "HDMI1_TX0_N_160") (pintype "passive"))
      (node (ref "P8") (pin "22") (pinfunction "22_22") (pintype "passive"))
    )
    (net (code "87") (name "/Pin163") (class "Default")
      (node (ref "P1") (pin "163") (pinfunction "DSI0_D1_N_163") (pintype "passive"))
      (node (ref "P9") (pin "38") (pinfunction "38_38") (pintype "passive"))
    )
    (net (code "88") (name "/Pin164") (class "Default")
      (node (ref "P1") (pin "164") (pinfunction "HDMI1_CLK_P_164") (pintype "passive"))
      (node (ref "P8") (pin "26") (pinfunction "26_26") (pintype "passive"))
    )
    (net (code "89") (name "/Pin165") (class "Default")
      (node (ref "P1") (pin "165") (pinfunction "DSI0_D1_P_165") (pintype "passive"))
      (node (ref "P9") (pin "40") (pinfunction "40_40") (pintype "passive"))
    )
    (net (code "90") (name "/Pin166") (class "Default")
      (node (ref "P1") (pin "166") (pinfunction "HDMI1_CLK_N_166") (pintype "passive"))
      (node (ref "P8") (pin "28") (pinfunction "28_28") (pintype "passive"))
    )
    (net (code "91") (name "/Pin169") (class "Default")
      (node (ref "P1") (pin "169") (pinfunction "DSI0_C_N_169") (pintype "passive"))
      (node (ref "P11") (pin "2") (pinfunction "2_2") (pintype "passive"))
    )
    (net (code "92") (name "/Pin170") (class "Default")
      (node (ref "P1") (pin "170") (pinfunction "HDMI0_TX2_P_170") (pintype "passive"))
      (node (ref "P8") (pin "32") (pinfunction "32_32") (pintype "passive"))
    )
    (net (code "93") (name "/Pin171") (class "Default")
      (node (ref "P1") (pin "171") (pinfunction "DSI0_C_P_171") (pintype "passive"))
      (node (ref "P11") (pin "4") (pinfunction "4_4") (pintype "passive"))
    )
    (net (code "94") (name "/Pin172") (class "Default")
      (node (ref "P1") (pin "172") (pinfunction "HDMI0_TX2_N_172") (pintype "passive"))
      (node (ref "P8") (pin "34") (pinfunction "34_34") (pintype "passive"))
    )
    (net (code "95") (name "/Pin175") (class "Default")
      (node (ref "P1") (pin "175") (pinfunction "DSI1_D0_N_175") (pintype "passive"))
      (node (ref "P11") (pin "8") (pinfunction "8_8") (pintype "passive"))
    )
    (net (code "96") (name "/Pin176") (class "Default")
      (node (ref "P1") (pin "176") (pinfunction "HDMI0_TX1_P_176") (pintype "passive"))
      (node (ref "P8") (pin "38") (pinfunction "38_38") (pintype "passive"))
    )
    (net (code "97") (name "/Pin177") (class "Default")
      (node (ref "P1") (pin "177") (pinfunction "DSI1_D0_P_177") (pintype "passive"))
      (node (ref "P11") (pin "10") (pinfunction "10_10") (pintype "passive"))
    )
    (net (code "98") (name "/Pin178") (class "Default")
      (node (ref "P1") (pin "178") (pinfunction "HDMI0_TX1_N_178") (pintype "passive"))
      (node (ref "P8") (pin "40") (pinfunction "40_40") (pintype "passive"))
    )
    (net (code "99") (name "/Pin181") (class "Default")
      (node (ref "P1") (pin "181") (pinfunction "DSI1_D1_N_181") (pintype "passive"))
      (node (ref "P11") (pin "14") (pinfunction "14_14") (pintype "passive"))
    )
    (net (code "100") (name "/Pin182") (class "Default")
      (node (ref "P1") (pin "182") (pinfunction "HDMI0_TX0_P_182") (pintype "passive"))
      (node (ref "P9") (pin "1") (pinfunction "1_1") (pintype "passive"))
    )
    (net (code "101") (name "/Pin183") (class "Default")
      (node (ref "P1") (pin "183") (pinfunction "DSI1_D1_P_183") (pintype "passive"))
      (node (ref "P11") (pin "16") (pinfunction "16_16") (pintype "passive"))
    )
    (net (code "102") (name "/Pin184") (class "Default")
      (node (ref "P1") (pin "184") (pinfunction "HDMI0_TX0_N_184") (pintype "passive"))
      (node (ref "P9") (pin "3") (pinfunction "3_3") (pintype "passive"))
    )
    (net (code "103") (name "/Pin187") (class "Default")
      (node (ref "P1") (pin "187") (pinfunction "DSI1_C_N_187") (pintype "passive"))
      (node (ref "P11") (pin "1") (pinfunction "1_1") (pintype "passive"))
    )
    (net (code "104") (name "/Pin188") (class "Default")
      (node (ref "P1") (pin "188") (pinfunction "HDMI0_CLK_P_188") (pintype "passive"))
      (node (ref "P9") (pin "7") (pinfunction "7_7") (pintype "passive"))
    )
    (net (code "105") (name "/Pin189") (class "Default")
      (node (ref "P1") (pin "189") (pinfunction "DSI1_C_P_189") (pintype "passive"))
      (node (ref "P11") (pin "3") (pinfunction "3_3") (pintype "passive"))
    )
    (net (code "106") (name "/Pin190") (class "Default")
      (node (ref "P1") (pin "190") (pinfunction "HDMI0_CLK_N_190") (pintype "passive"))
      (node (ref "P9") (pin "9") (pinfunction "9_9") (pintype "passive"))
    )
    (net (code "107") (name "/Pin193") (class "Default")
      (node (ref "P1") (pin "193") (pinfunction "DSI1_D2_N_193") (pintype "passive"))
      (node (ref "P11") (pin "7") (pinfunction "7_7") (pintype "passive"))
    )
    (net (code "108") (name "/Pin194") (class "Default")
      (node (ref "P1") (pin "194") (pinfunction "DSI1_D3_N_194") (pintype "passive"))
      (node (ref "P9") (pin "13") (pinfunction "13_13") (pintype "passive"))
    )
    (net (code "109") (name "/Pin195") (class "Default")
      (node (ref "P1") (pin "195") (pinfunction "DSI1_D2_P_195") (pintype "passive"))
      (node (ref "P11") (pin "9") (pinfunction "9_9") (pintype "passive"))
    )
    (net (code "110") (name "/Pin196") (class "Default")
      (node (ref "P1") (pin "196") (pinfunction "DSI1_D3_P_196") (pintype "passive"))
      (node (ref "P9") (pin "15") (pinfunction "15_15") (pintype "passive"))
    )
    (net (code "111") (name "/Pin199") (class "Default")
      (node (ref "P1") (pin "199") (pinfunction "HDMI0_SDA_199") (pintype "passive"))
      (node (ref "P9") (pin "27") (pinfunction "27_27") (pintype "passive"))
    )
    (net (code "112") (name "/Pin200") (class "Default")
      (node (ref "P1") (pin "200") (pinfunction "HDMI0_SCL_200") (pintype "passive"))
      (node (ref "P9") (pin "29") (pinfunction "29_29") (pintype "passive"))
    )
    (net (code "113") (name "/RUN_PG") (class "Default")
      (node (ref "P2") (pin "92") (pinfunction "RUN_PG_92") (pintype "passive"))
      (node (ref "U3") (pin "2") (pinfunction "A_2") (pintype "passive"))
    )
    (net (code "114") (name "/SCL0") (class "Default")
      (node (ref "P10") (pin "22") (pinfunction "22_22") (pintype "passive"))
      (node (ref "P2") (pin "80") (pinfunction "SCL0_80") (pintype "passive"))
    )
    (net (code "115") (name "/SDA0") (class "Default")
      (node (ref "P10") (pin "24") (pinfunction "24_24") (pintype "passive"))
      (node (ref "P2") (pin "82") (pinfunction "SDA0_82") (pintype "passive"))
    )
    (net (code "116") (name "/SD_CLK") (class "Default")
      (node (ref "P10") (pin "7") (pinfunction "7_7") (pintype "passive"))
      (node (ref "P2") (pin "57") (pinfunction "SD_CLK_57") (pintype "passive"))
    )
    (net (code "117") (name "/SD_CMD") (class "Default")
      (node (ref "P10") (pin "8") (pinfunction "8_8") (pintype "passive"))
      (node (ref "P2") (pin "62") (pinfunction "SD_CMD_62") (pintype "passive"))
    )
    (net (code "118") (name "/SD_DAT0") (class "Default")
      (node (ref "P10") (pin "11") (pinfunction "11_11") (pintype "passive"))
      (node (ref "P2") (pin "63") (pinfunction "SD_DATO_63") (pintype "passive"))
    )
    (net (code "119") (name "/SD_DAT1") (class "Default")
      (node (ref "P10") (pin "17") (pinfunction "17_17") (pintype "passive"))
      (node (ref "P2") (pin "67") (pinfunction "SD_DAT1_67") (pintype "passive"))
    )
    (net (code "120") (name "/SD_DAT2") (class "Default")
      (node (ref "P10") (pin "19") (pinfunction "19_19") (pintype "passive"))
      (node (ref "P2") (pin "69") (pinfunction "SD_DAT2_69") (pintype "passive"))
    )
    (net (code "121") (name "/SD_DAT3") (class "Default")
      (node (ref "P10") (pin "13") (pinfunction "13_13") (pintype "passive"))
      (node (ref "P2") (pin "61") (pinfunction "SD_DAT3_61") (pintype "passive"))
    )
    (net (code "122") (name "/SD_PWR_ON") (class "Default")
      (node (ref "P10") (pin "25") (pinfunction "25_25") (pintype "passive"))
      (node (ref "P2") (pin "75") (pinfunction "SD_PWR_ON_75") (pintype "passive"))
    )
    (net (code "123") (name "/SYNC_IN") (class "Default")
      (node (ref "P12") (pin "8") (pinfunction "8_8") (pintype "passive"))
      (node (ref "P2") (pin "16") (pinfunction "Ethernet_SYNC_IN_16") (pintype "passive"))
    )
    (net (code "124") (name "/SYNC_OUT") (class "Default")
      (node (ref "P12") (pin "9") (pinfunction "9_9") (pintype "passive"))
      (node (ref "P2") (pin "18") (pinfunction "Ethernet_SYNC_OUT_18") (pintype "passive"))
    )
    (net (code "125") (name "/TV_OUT") (class "Default")
      (node (ref "P1") (pin "111") (pinfunction "VDAC_COMP_111") (pintype "passive"))
      (node (ref "P12") (pin "11") (pinfunction "11_11") (pintype "passive"))
    )
    (net (code "126") (name "/VCC") (class "Default")
      (node (ref "C2") (pin "1") (pintype "passive"))
      (node (ref "C4") (pin "1") (pintype "passive"))
      (node (ref "P6") (pin "13") (pinfunction "VCC+_13") (pintype "passive"))
      (node (ref "P6") (pin "15") (pinfunction "VCC+_15") (pintype "passive"))
      (node (ref "P7") (pin "1") (pinfunction "1_1") (pintype "passive"))
      (node (ref "P7") (pin "2") (pinfunction "2_2") (pintype "passive"))
    )
    (net (code "127") (name "/WL_nDisable") (class "Default")
      (node (ref "P10") (pin "29") (pinfunction "29_29") (pintype "passive"))
      (node (ref "P2") (pin "89") (pinfunction "WL_nDisable_89") (pintype "passive"))
    )
    (net (code "128") (name "/nEXTRST") (class "Default")
      (node (ref "P10") (pin "40") (pinfunction "40_40") (pintype "passive"))
      (node (ref "P2") (pin "100") (pinfunction "nEXTRST_100") (pintype "passive"))
    )
    (net (code "129") (name "/nPWR_LED") (class "Default")
      (node (ref "P2") (pin "95") (pinfunction "PI_LED_nPWR_95") (pintype "passive"))
      (node (ref "U4") (pin "2") (pinfunction "A_2") (pintype "passive"))
    )
    (net (code "130") (name "/nRPIBOOT") (class "Default")
      (node (ref "P12") (pin "2") (pinfunction "2_2") (pintype "passive"))
      (node (ref "P2") (pin "93") (pinfunction "nRPIBOOT_93") (pintype "passive"))
    )
    (net (code "131") (name "3V3") (class "Default")
      (node (ref "H1") (pin "1") (pinfunction "ANODE_1") (pintype "passive"))
      (node (ref "H2") (pin "1") (pinfunction "ANODE_1") (pintype "passive"))
      (node (ref "P10") (pin "26") (pinfunction "26_26") (pintype "passive"))
      (node (ref "P2") (pin "78") (pinfunction "GPIO_VREF_78") (pintype "passive"))
      (node (ref "P2") (pin "84") (pinfunction "CM4_3.3V_(Output)_84") (pintype "passive"))
      (node (ref "P2") (pin "86") (pinfunction "CM4_3.3V_(Output)_86") (pintype "passive"))
      (node (ref "P3") (pin "1") (pinfunction "1_1") (pintype "passive"))
      (node (ref "P3") (pin "17") (pinfunction "17_17") (pintype "passive"))
      (node (ref "U4") (pin "5") (pinfunction "VCC_5") (pintype "passive"))
    )
    (net (code "132") (name "5V") (class "Default")
      (node (ref "P2") (pin "77") (pinfunction "+5V_(Input)_77") (pintype "passive"))
      (node (ref "P2") (pin "79") (pinfunction "+5V_(Input)_79") (pintype "passive"))
      (node (ref "P2") (pin "81") (pinfunction "+5V_(Input)_81") (pintype "passive"))
      (node (ref "P2") (pin "83") (pinfunction "+5V_(Input)_83") (pintype "passive"))
      (node (ref "P2") (pin "85") (pinfunction "+5V_(Input)_85") (pintype "passive"))
      (node (ref "P2") (pin "87") (pinfunction "+5V_(Input)_87") (pintype "passive"))
      (node (ref "P3") (pin "2") (pinfunction "2_2") (pintype "passive"))
      (node (ref "P3") (pin "4") (pinfunction "4_4") (pintype "passive"))
      (node (ref "P4") (pin "1") (pinfunction "1_1") (pintype "passive"))
      (node (ref "P5") (pin "1") (pinfunction "Vbus_1") (pintype "passive"))
      (node (ref "U3") (pin "5") (pinfunction "VCC_5") (pintype "passive"))
    )
    (net (code "133") (name "GND") (class "Default")
      (node (ref "C6") (pin "1") (pintype "passive"))
      (node (ref "P1") (pin "107") (pinfunction "GND_107") (pintype "passive"))
      (node (ref "P1") (pin "108") (pinfunction "GND_108") (pintype "passive"))
      (node (ref "P1") (pin "113") (pinfunction "GND_113") (pintype "passive"))
      (node (ref "P1") (pin "114") (pinfunction "GND_114") (pintype "passive"))
      (node (ref "P1") (pin "119") (pinfunction "GND_119") (pintype "passive"))
      (node (ref "P1") (pin "120") (pinfunction "GND_120") (pintype "passive"))
      (node (ref "P1") (pin "125") (pinfunction "GND_125") (pintype "passive"))
      (node (ref "P1") (pin "126") (pinfunction "GND_126") (pintype "passive"))
      (node (ref "P1") (pin "131") (pinfunction "GND_131") (pintype "passive"))
      (node (ref "P1") (pin "132") (pinfunction "GND_132") (pintype "passive"))
      (node (ref "P1") (pin "137") (pinfunction "GND_137") (pintype "passive"))
      (node (ref "P1") (pin "138") (pinfunction "GND_138") (pintype "passive"))
      (node (ref "P1") (pin "144") (pinfunction "GND_144") (pintype "passive"))
      (node (ref "P1") (pin "150") (pinfunction "GND_150") (pintype "passive"))
      (node (ref "P1") (pin "155") (pinfunction "GND_155") (pintype "passive"))
      (node (ref "P1") (pin "156") (pinfunction "GND_156") (pintype "passive"))
      (node (ref "P1") (pin "161") (pinfunction "GND_161") (pintype "passive"))
      (node (ref "P1") (pin "162") (pinfunction "GND_162") (pintype "passive"))
      (node (ref "P1") (pin "167") (pinfunction "GND_167") (pintype "passive"))
      (node (ref "P1") (pin "168") (pinfunction "GND_168") (pintype "passive"))
      (node (ref "P1") (pin "173") (pinfunction "GND_173") (pintype "passive"))
      (node (ref "P1") (pin "174") (pinfunction "GND_174") (pintype "passive"))
      (node (ref "P1") (pin "179") (pinfunction "GND_179") (pintype "passive"))
      (node (ref "P1") (pin "180") (pinfunction "GND_180") (pintype "passive"))
      (node (ref "P1") (pin "185") (pinfunction "GND_185") (pintype "passive"))
      (node (ref "P1") (pin "186") (pinfunction "GND_186") (pintype "passive"))
      (node (ref "P1") (pin "191") (pinfunction "GND_191") (pintype "passive"))
      (node (ref "P1") (pin "192") (pinfunction "GND_192") (pintype "passive"))
      (node (ref "P1") (pin "197") (pinfunction "GND_197") (pintype "passive"))
      (node (ref "P1") (pin "198") (pinfunction "GND_198") (pintype "passive"))
      (node (ref "P10") (pin "10") (pinfunction "10_10") (pintype "passive"))
      (node (ref "P10") (pin "12") (pinfunction "12_12") (pintype "passive"))
      (node (ref "P10") (pin "14") (pinfunction "14_14") (pintype "passive"))
      (node (ref "P10") (pin "15") (pinfunction "15_15") (pintype "passive"))
      (node (ref "P10") (pin "16") (pinfunction "16_16") (pintype "passive"))
      (node (ref "P10") (pin "18") (pinfunction "18_18") (pintype "passive"))
      (node (ref "P10") (pin "2") (pinfunction "2_2") (pintype "passive"))
      (node (ref "P10") (pin "20") (pinfunction "20_20") (pintype "passive"))
      (node (ref "P10") (pin "21") (pinfunction "21_21") (pintype "passive"))
      (node (ref "P10") (pin "27") (pinfunction "27_27") (pintype "passive"))
      (node (ref "P10") (pin "32") (pinfunction "32_32") (pintype "passive"))
      (node (ref "P10") (pin "33") (pinfunction "33_33") (pintype "passive"))
      (node (ref "P10") (pin "34") (pinfunction "34_34") (pintype "passive"))
      (node (ref "P10") (pin "35") (pinfunction "35_35") (pintype "passive"))
      (node (ref "P10") (pin "36") (pinfunction "36_36") (pintype "passive"))
      (node (ref "P10") (pin "38") (pinfunction "38_38") (pintype "passive"))
      (node (ref "P10") (pin "39") (pinfunction "39_39") (pintype "passive"))
      (node (ref "P10") (pin "4") (pinfunction "4_4") (pintype "passive"))
      (node (ref "P10") (pin "5") (pinfunction "5_5") (pintype "passive"))
      (node (ref "P10") (pin "6") (pinfunction "6_6") (pintype "passive"))
      (node (ref "P10") (pin "9") (pinfunction "9_9") (pintype "passive"))
      (node (ref "P11") (pin "11") (pinfunction "11_11") (pintype "passive"))
      (node (ref "P11") (pin "12") (pinfunction "12_12") (pintype "passive"))
      (node (ref "P11") (pin "13") (pinfunction "13_13") (pintype "passive"))
      (node (ref "P11") (pin "15") (pinfunction "15_15") (pintype "passive"))
      (node (ref "P11") (pin "17") (pinfunction "17_17") (pintype "passive"))
      (node (ref "P11") (pin "18") (pinfunction "18_18") (pintype "passive"))
      (node (ref "P11") (pin "19") (pinfunction "19_19") (pintype "passive"))
      (node (ref "P11") (pin "20") (pinfunction "20_20") (pintype "passive"))
      (node (ref "P11") (pin "5") (pinfunction "5_5") (pintype "passive"))
      (node (ref "P11") (pin "6") (pinfunction "6_6") (pintype "passive"))
      (node (ref "P12") (pin "1") (pinfunction "1_1") (pintype "passive"))
      (node (ref "P12") (pin "10") (pinfunction "10_10") (pintype "passive"))
      (node (ref "P12") (pin "12") (pinfunction "12_12") (pintype "passive"))
      (node (ref "P12") (pin "3") (pinfunction "3_3") (pintype "passive"))
      (node (ref "P12") (pin "7") (pinfunction "7_7") (pintype "passive"))
      (node (ref "P2") (pin "1") (pinfunction "GND_1") (pintype "passive"))
      (node (ref "P2") (pin "13") (pinfunction "GND_13") (pintype "passive"))
      (node (ref "P2") (pin "14") (pinfunction "GND_14") (pintype "passive"))
      (node (ref "P2") (pin "2") (pinfunction "GND_2") (pintype "passive"))
      (node (ref "P2") (pin "22") (pinfunction "GND_22") (pintype "passive"))
      (node (ref "P2") (pin "23") (pinfunction "GND_23") (pintype "passive"))
      (node (ref "P2") (pin "32") (pinfunction "GND_32") (pintype "passive"))
      (node (ref "P2") (pin "33") (pinfunction "GND_33") (pintype "passive"))
      (node (ref "P2") (pin "42") (pinfunction "GND_42") (pintype "passive"))
      (node (ref "P2") (pin "43") (pinfunction "GND_43") (pintype "passive"))
      (node (ref "P2") (pin "52") (pinfunction "GND_52") (pintype "passive"))
      (node (ref "P2") (pin "53") (pinfunction "GND_53") (pintype "passive"))
      (node (ref "P2") (pin "59") (pinfunction "GND_59") (pintype "passive"))
      (node (ref "P2") (pin "60") (pinfunction "GND_60") (pintype "passive"))
      (node (ref "P2") (pin "65") (pinfunction "GND_65") (pintype "passive"))
      (node (ref "P2") (pin "66") (pinfunction "GND_66") (pintype "passive"))
      (node (ref "P2") (pin "7") (pinfunction "GND_7") (pintype "passive"))
      (node (ref "P2") (pin "71") (pinfunction "GND_71") (pintype "passive"))
      (node (ref "P2") (pin "74") (pinfunction "GND_74") (pintype "passive"))
      (node (ref "P2") (pin "8") (pinfunction "GND_8") (pintype "passive"))
      (node (ref "P2") (pin "98") (pinfunction "GND_98") (pintype "passive"))
      (node (ref "P3") (pin "14") (pinfunction "14_14") (pintype "passive"))
      (node (ref "P3") (pin "20") (pinfunction "20_20") (pintype "passive"))
      (node (ref "P3") (pin "25") (pinfunction "25_25") (pintype "passive"))
      (node (ref "P3") (pin "30") (pinfunction "30_30") (pintype "passive"))
      (node (ref "P3") (pin "34") (pinfunction "34_34") (pintype "passive"))
      (node (ref "P3") (pin "39") (pinfunction "39_39") (pintype "passive"))
      (node (ref "P3") (pin "6") (pinfunction "6_6") (pintype "passive"))
      (node (ref "P3") (pin "9") (pinfunction "9_9") (pintype "passive"))
      (node (ref "P4") (pin "2") (pinfunction "2_2") (pintype "passive"))
      (node (ref "P4") (pin "3") (pinfunction "3_3") (pintype "passive"))
      (node (ref "P5") (pin "4") (pinfunction "GND_4") (pintype "passive"))
      (node (ref "P8") (pin "12") (pinfunction "12_12") (pintype "passive"))
      (node (ref "P8") (pin "13") (pinfunction "13_13") (pintype "passive"))
      (node (ref "P8") (pin "18") (pinfunction "18_18") (pintype "passive"))
      (node (ref "P8") (pin "19") (pinfunction "19_19") (pintype "passive"))
      (node (ref "P8") (pin "24") (pinfunction "24_24") (pintype "passive"))
      (node (ref "P8") (pin "25") (pinfunction "25_25") (pintype "passive"))
      (node (ref "P8") (pin "3") (pinfunction "3_3") (pintype "passive"))
      (node (ref "P8") (pin "30") (pinfunction "30_30") (pintype "passive"))
      (node (ref "P8") (pin "31") (pinfunction "31_31") (pintype "passive"))
      (node (ref "P8") (pin "36") (pinfunction "36_36") (pintype "passive"))
      (node (ref "P8") (pin "37") (pinfunction "37_37") (pintype "passive"))
      (node (ref "P8") (pin "39") (pinfunction "39_39") (pintype "passive"))
      (node (ref "P8") (pin "5") (pinfunction "5_5") (pintype "passive"))
      (node (ref "P8") (pin "6") (pinfunction "6_6") (pintype "passive"))
      (node (ref "P8") (pin "7") (pinfunction "7_7") (pintype "passive"))
      (node (ref "P9") (pin "11") (pinfunction "11_11") (pintype "passive"))
      (node (ref "P9") (pin "12") (pinfunction "12_12") (pintype "passive"))
      (node (ref "P9") (pin "17") (pinfunction "17_17") (pintype "passive"))
      (node (ref "P9") (pin "18") (pinfunction "18_18") (pintype "passive"))
      (node (ref "P9") (pin "19") (pinfunction "19_19") (pintype "passive"))
      (node (ref "P9") (pin "23") (pinfunction "23_23") (pintype "passive"))
      (node (ref "P9") (pin "24") (pinfunction "24_24") (pintype "passive"))
      (node (ref "P9") (pin "36") (pinfunction "36_36") (pintype "passive"))
      (node (ref "P9") (pin "5") (pinfunction "5_5") (pintype "passive"))
      (node (ref "P9") (pin "6") (pinfunction "6_6") (pintype "passive"))
      (node (ref "U1") (pin "3") (pinfunction "GND_3") (pintype "passive"))
      (node (ref "U2") (pin "3") (pinfunction "GND_3") (pintype "passive"))
      (node (ref "U3") (pin "3") (pinfunction "GND_3") (pintype "passive"))
      (node (ref "U4") (pin "3") (pinfunction "GND_3") (pintype "passive"))
    )
    (net (code "134") (name "GND_T") (class "Default")
      (node (ref "C1") (pin "1") (pintype "passive"))
      (node (ref "C3") (pin "1") (pintype "passive"))
      (node (ref "C5") (pin "2") (pintype "passive"))
      (node (ref "P6") (pin "14") (pinfunction "VCC-_14") (pintype "passive"))
      (node (ref "P6") (pin "16") (pinfunction "VCC-_16") (pintype "passive"))
      (node (ref "P7") (pin "3") (pinfunction "3_3") (pintype "passive"))
      (node (ref "P7") (pin "4") (pinfunction "4_4") (pintype "passive"))
    )
    (net (code "135") (name "Net-(C1-Pad2)") (class "Default")
      (node (ref "C1") (pin "2") (pintype "passive"))
      (node (ref "R2") (pin "2") (pinfunction "2_2") (pintype "passive"))
    )
    (net (code "136") (name "Net-(C2-Pad2)") (class "Default")
      (node (ref "C2") (pin "2") (pintype "passive"))
      (node (ref "R3") (pin "2") (pinfunction "2_2") (pintype "passive"))
    )
    (net (code "137") (name "Net-(C3-Pad2)") (class "Default")
      (node (ref "C3") (pin "2") (pintype "passive"))
      (node (ref "R4") (pin "2") (pinfunction "2_2") (pintype "passive"))
    )
    (net (code "138") (name "Net-(C4-Pad2)") (class "Default")
      (node (ref "C4") (pin "2") (pintype "passive"))
      (node (ref "R5") (pin "2") (pinfunction "2_2") (pintype "passive"))
    )
    (net (code "139") (name "Net-(C5-Pad1)") (class "Default")
      (node (ref "C5") (pin "1") (pintype "passive"))
      (node (ref "R2") (pin "1") (pinfunction "1_1") (pintype "passive"))
      (node (ref "R3") (pin "1") (pinfunction "1_1") (pintype "passive"))
      (node (ref "R4") (pin "1") (pinfunction "1_1") (pintype "passive"))
      (node (ref "R5") (pin "1") (pinfunction "1_1") (pintype "passive"))
    )
    (net (code "140") (name "Net-(H1-CATHODE)") (class "Default")
      (node (ref "H1") (pin "2") (pinfunction "CATHODE_2") (pintype "passive"))
      (node (ref "R1") (pin "2") (pinfunction "2_2") (pintype "passive"))
    )
    (net (code "141") (name "Net-(H2-CATHODE)") (class "Default")
      (node (ref "H2") (pin "2") (pinfunction "CATHODE_2") (pintype "passive"))
      (node (ref "R6") (pin "2") (pinfunction "2_2") (pintype "passive"))
    )
    (net (code "142") (name "Net-(P2-PI_nLED_Activity)") (class "Default")
      (node (ref "P2") (pin "21") (pinfunction "PI_nLED_Activity_21") (pintype "passive"))
      (node (ref "R1") (pin "1") (pinfunction "1_1") (pintype "passive"))
    )
    (net (code "143") (name "Net-(P6-TRCT1)") (class "Default")
      (node (ref "C6") (pin "2") (pintype "passive"))
      (node (ref "P6") (pin "1") (pinfunction "TRCT3_1") (pintype "passive"))
      (node (ref "P6") (pin "12") (pinfunction "TRCT1_12") (pintype "passive"))
      (node (ref "P6") (pin "6") (pinfunction "TRCT2_6") (pintype "passive"))
      (node (ref "P6") (pin "7") (pinfunction "TRCT4_7") (pintype "passive"))
    )
    (net (code "144") (name "Net-(U3-Y)") (class "Default")
      (node (ref "P12") (pin "13") (pinfunction "13_13") (pintype "passive"))
      (node (ref "U3") (pin "4") (pinfunction "Y_4") (pintype "passive"))
    )
    (net (code "145") (name "Net-(U4-Y)") (class "Default")
      (node (ref "R6") (pin "1") (pinfunction "1_1") (pintype "passive"))
      (node (ref "U4") (pin "4") (pinfunction "Y_4") (pintype "passive"))
    )
    (net (code "146") (name "unconnected-(P1-Reserved-Pad104)") (class "Default")
      (node (ref "P1") (pin "104") (pinfunction "Reserved_104") (pintype "passive"))
    )
    (net (code "147") (name "unconnected-(P1-Reserved-Pad106)") (class "Default")
      (node (ref "P1") (pin "106") (pinfunction "Reserved_106") (pintype "passive"))
    )
    (net (code "148") (name "unconnected-(P2-Ethernet_nLED1(3.3v)-Pad19)") (class "Default")
      (node (ref "P2") (pin "19") (pinfunction "Ethernet_nLED1(3.3v)_19") (pintype "passive"))
    )
    (net (code "149") (name "unconnected-(P2-Reserved-Pad76)") (class "Default")
      (node (ref "P2") (pin "76") (pinfunction "Reserved_76") (pintype "passive"))
    )
    (net (code "150") (name "unconnected-(P2-SD_DAT4-Pad68)") (class "Default")
      (node (ref "P2") (pin "68") (pinfunction "SD_DAT4_68") (pintype "passive"))
    )
    (net (code "151") (name "unconnected-(P2-SD_DAT5-Pad64)") (class "Default")
      (node (ref "P2") (pin "64") (pinfunction "SD_DAT5_64") (pintype "passive"))
    )
    (net (code "152") (name "unconnected-(P2-SD_DAT6-Pad72)") (class "Default")
      (node (ref "P2") (pin "72") (pinfunction "SD_DAT6_72") (pintype "passive"))
    )
    (net (code "153") (name "unconnected-(P2-SD_DAT7-Pad70)") (class "Default")
      (node (ref "P2") (pin "70") (pinfunction "SD_DAT7_70") (pintype "passive"))
    )
    (net (code "154") (name "unconnected-(P2-SD_VDD_Override-Pad73)") (class "Default")
      (node (ref "P2") (pin "73") (pinfunction "SD_VDD_Override_73") (pintype "passive"))
    )
    (net (code "155") (name "unconnected-(P10-Pad23)") (class "Default")
      (node (ref "P10") (pin "23") (pinfunction "23_23") (pintype "passive"))
    )
    (net (code "156") (name "unconnected-(U1-NC-Pad6)") (class "Default")
      (node (ref "U1") (pin "6") (pinfunction "NC_6") (pintype "passive"))
    )
    (net (code "157") (name "unconnected-(U1-NC-Pad7)") (class "Default")
      (node (ref "U1") (pin "7") (pinfunction "NC_7") (pintype "passive"))
    )
    (net (code "158") (name "unconnected-(U1-NC-Pad9)") (class "Default")
      (node (ref "U1") (pin "9") (pinfunction "NC_9") (pintype "passive"))
    )
    (net (code "159") (name "unconnected-(U1-NC-Pad10)") (class "Default")
      (node (ref "U1") (pin "10") (pinfunction "NC_10") (pintype "passive"))
    )
    (net (code "160") (name "unconnected-(U2-NC-Pad6)") (class "Default")
      (node (ref "U2") (pin "6") (pinfunction "NC_6") (pintype "passive"))
    )
    (net (code "161") (name "unconnected-(U2-NC-Pad7)") (class "Default")
      (node (ref "U2") (pin "7") (pinfunction "NC_7") (pintype "passive"))
    )
    (net (code "162") (name "unconnected-(U2-NC-Pad9)") (class "Default")
      (node (ref "U2") (pin "9") (pinfunction "NC_9") (pintype "passive"))
    )
    (net (code "163") (name "unconnected-(U2-NC-Pad10)") (class "Default")
      (node (ref "U2") (pin "10") (pinfunction "NC_10") (pintype "passive"))
    )
    (net (code "164") (name "unconnected-(U3-NC-Pad1)") (class "Default")
      (node (ref "U3") (pin "1") (pinfunction "NC_1") (pintype "passive"))
    )
    (net (code "165") (name "unconnected-(U4-NC-Pad1)") (class "Default")
      (node (ref "U4") (pin "1") (pinfunction "NC_1") (pintype "passive"))
    )
  )
)
